# 12V_to_5V_LDO_1A.net
KiCad netlist of a schematic drawn in Altium Designer
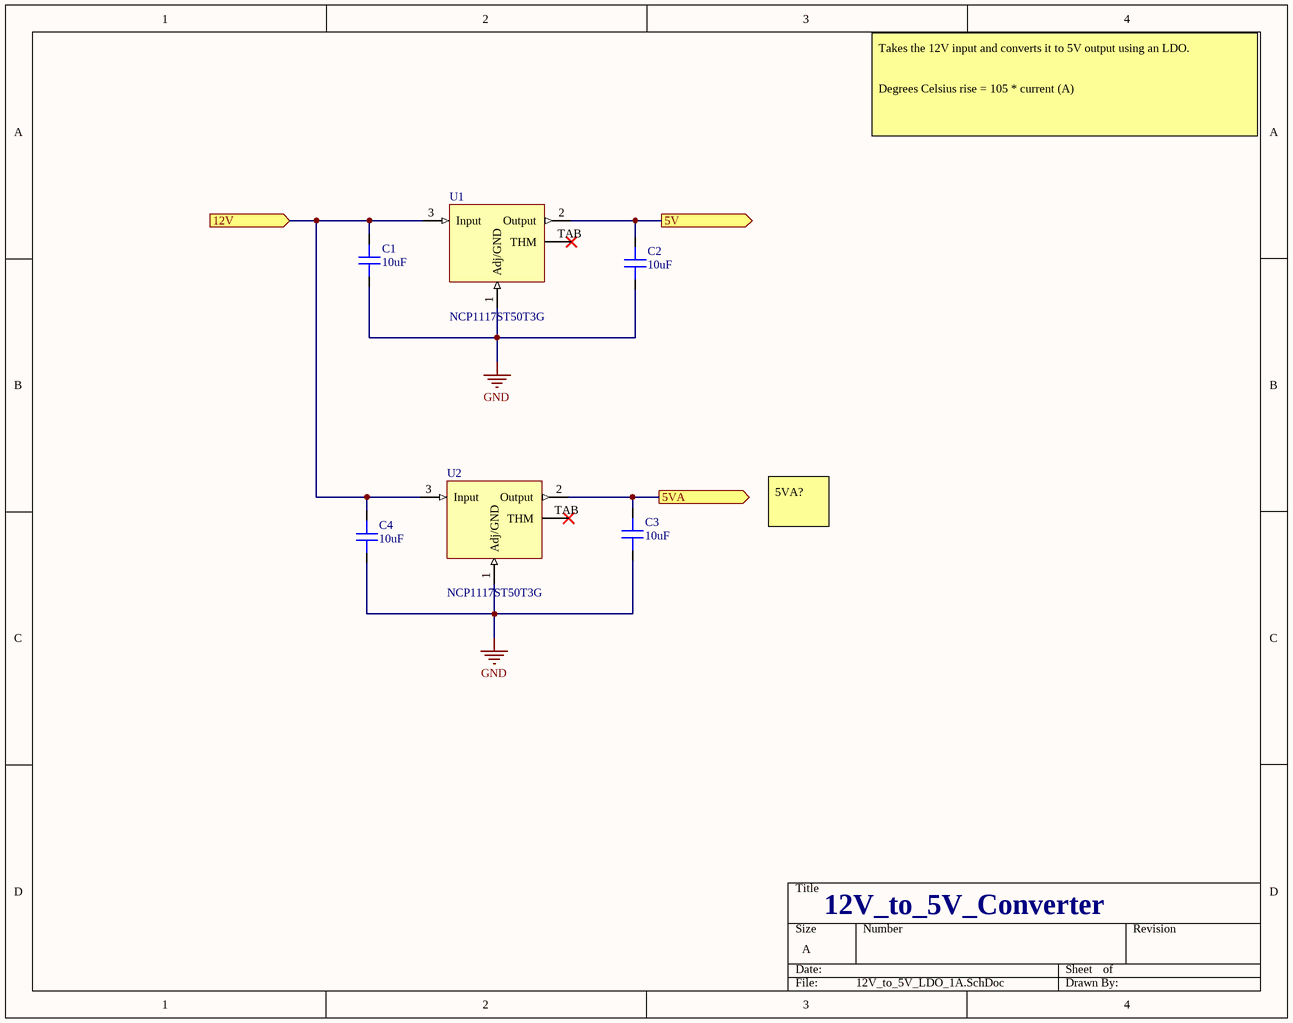
[diagram p0: 12V_to_5V_LDO_1A.SchDoc]

(export (version "E")
  (design (tool "Eeschema 10.0.6"))
  (components
    (comp (ref "C1")
      (value "capacitor")
      (footprint "0603")
      (description "Generic 0603 capacitor")
      (fields (field (name "CAPACITANCE") "10uF") (field (name "VOLTAGE") "50"))
      (libsource (lib "altlib") (part "capacitor"))
    )
    (comp (ref "C2")
      (value "capacitor")
      (footprint "0603")
      (description "Generic 0603 capacitor")
      (fields (field (name "CAPACITANCE") "10uF") (field (name "VOLTAGE") "50"))
      (libsource (lib "altlib") (part "capacitor"))
    )
    (comp (ref "C3")
      (value "capacitor")
      (footprint "0603")
      (description "Generic 0603 capacitor")
      (fields (field (name "CAPACITANCE") "10uF") (field (name "VOLTAGE") "50"))
      (libsource (lib "altlib") (part "capacitor"))
    )
    (comp (ref "C4")
      (value "capacitor")
      (footprint "0603")
      (description "Generic 0603 capacitor")
      (fields (field (name "CAPACITANCE") "10uF") (field (name "VOLTAGE") "50"))
      (libsource (lib "altlib") (part "capacitor"))
    )
    (comp (ref "U1")
      (value "NCP1117ST50T3G")
      (footprint "SOT-223-3")
      (description "5V linear regulator")
      (libsource (lib "altlib") (part "NCP1117ST50T3G"))
    )
    (comp (ref "U2")
      (value "NCP1117ST50T3G")
      (footprint "SOT-223-3")
      (description "5V linear regulator")
      (libsource (lib "altlib") (part "NCP1117ST50T3G"))
    )
  )
  (nets
    (net (code "1") (name "/5V") (class "Default")
      (node (ref "C2") (pin "2") (pinfunction "2_2") (pintype "passive"))
      (node (ref "U1") (pin "2") (pinfunction "Output_2") (pintype "output"))
    )
    (net (code "2") (name "/5VA") (class "Default")
      (node (ref "C3") (pin "2") (pinfunction "2_2") (pintype "passive"))
      (node (ref "U2") (pin "2") (pinfunction "Output_2") (pintype "output"))
    )
    (net (code "3") (name "/12V") (class "Default")
      (node (ref "C1") (pin "2") (pinfunction "2_2") (pintype "passive"))
      (node (ref "C4") (pin "2") (pinfunction "2_2") (pintype "passive"))
      (node (ref "U1") (pin "3") (pinfunction "Input_3") (pintype "input"))
      (node (ref "U2") (pin "3") (pinfunction "Input_3") (pintype "input"))
    )
    (net (code "4") (name "GND") (class "Default")
      (node (ref "C1") (pin "1") (pinfunction "1_1") (pintype "passive"))
      (node (ref "C2") (pin "1") (pinfunction "1_1") (pintype "passive"))
      (node (ref "C3") (pin "1") (pinfunction "1_1") (pintype "passive"))
      (node (ref "C4") (pin "1") (pinfunction "1_1") (pintype "passive"))
      (node (ref "U1") (pin "1") (pinfunction "Adj/GND_1") (pintype "input"))
      (node (ref "U2") (pin "1") (pinfunction "Adj/GND_1") (pintype "input"))
    )
    (net (code "5") (name "unconnected-(U1-THM-PadTAB)") (class "Default")
      (node (ref "U1") (pin "TAB") (pinfunction "THM_TAB") (pintype "passive+no_connect"))
    )
    (net (code "6") (name "unconnected-(U2-THM-PadTAB)") (class "Default")
      (node (ref "U2") (pin "TAB") (pinfunction "THM_TAB") (pintype "passive+no_connect"))
    )
  )
)
